# indicator.net
KiCad netlist of a schematic drawn in Altium Designer
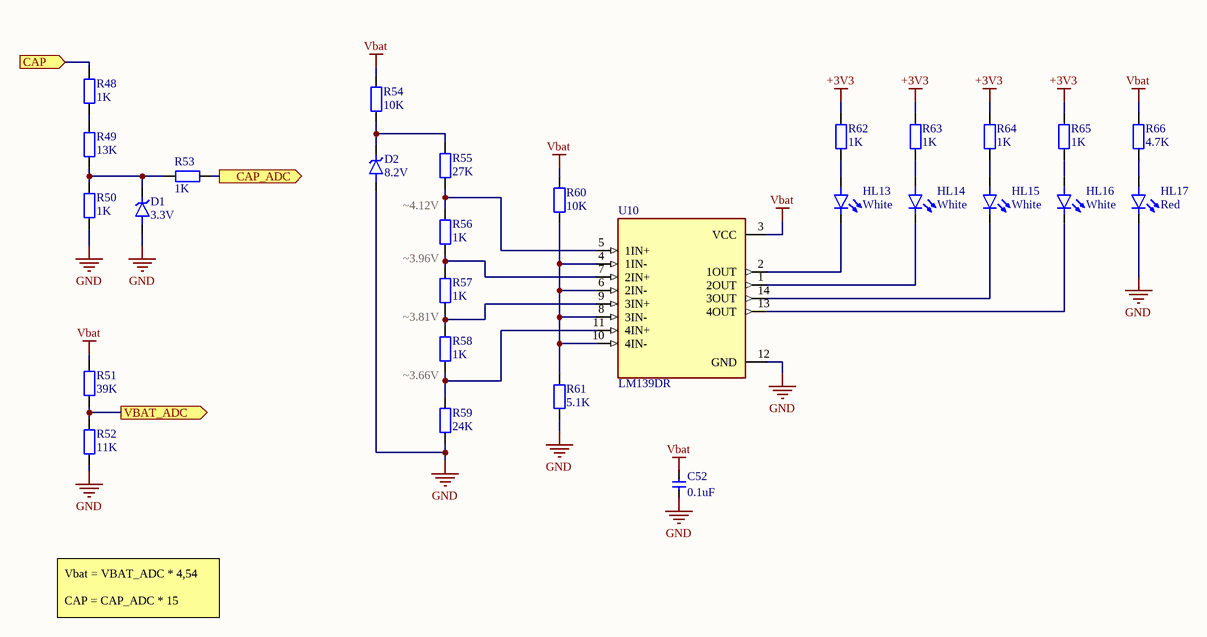
[diagram p0: indicator.SchDoc]

(export (version "E")
  (design (tool "Eeschema 10.0.6"))
  (components
    (comp (ref "C52")
      (value "0.1uF")
      (footprint "CAP0805")
      (description "Ceramic SMD Cap")
      (libsource (lib "Asterisk") (part "CAP Ceramic"))
    )
    (comp (ref "D1")
      (value "3.3V")
      (footprint "SOD-80")
      (description "Zener Diode\r\nBZV55C8V2")
      (libsource (lib "Asterisk") (part "Diode Zener"))
    )
    (comp (ref "D2")
      (value "8.2V")
      (footprint "SOD-80")
      (description "Zener Diode\r\nBZV55C8V2")
      (libsource (lib "Asterisk") (part "Diode Zener"))
    )
    (comp (ref "HL13")
      (value "White")
      (footprint "LED0603_GREEN")
      (description "LED smd")
      (libsource (lib "Asterisk") (part "LED"))
    )
    (comp (ref "HL14")
      (value "White")
      (footprint "LED0603_GREEN")
      (description "LED smd")
      (libsource (lib "Asterisk") (part "LED"))
    )
    (comp (ref "HL15")
      (value "White")
      (footprint "LED0603_GREEN")
      (description "LED smd")
      (libsource (lib "Asterisk") (part "LED"))
    )
    (comp (ref "HL16")
      (value "White")
      (footprint "LED0603_GREEN")
      (description "LED smd")
      (libsource (lib "Asterisk") (part "LED"))
    )
    (comp (ref "HL17")
      (value "Red")
      (footprint "LED0603_RED")
      (description "LED smd")
      (libsource (lib "Asterisk") (part "LED"))
    )
    (comp (ref "R48")
      (value "1K")
      (footprint "RES0805")
      (description "RES smd")
      (libsource (lib "Asterisk") (part "RES"))
    )
    (comp (ref "R49")
      (value "13K")
      (footprint "RES0805")
      (description "RES smd")
      (libsource (lib "Asterisk") (part "RES"))
    )
    (comp (ref "R50")
      (value "1K")
      (footprint "RES0805")
      (description "RES smd")
      (libsource (lib "Asterisk") (part "RES"))
    )
    (comp (ref "R51")
      (value "39K")
      (footprint "RES0805")
      (description "RES smd")
      (libsource (lib "Asterisk") (part "RES"))
    )
    (comp (ref "R52")
      (value "11K")
      (footprint "RES0805")
      (description "RES smd")
      (libsource (lib "Asterisk") (part "RES"))
    )
    (comp (ref "R53")
      (value "1K")
      (footprint "RES0805")
      (description "RES smd")
      (libsource (lib "Asterisk") (part "RES"))
    )
    (comp (ref "R54")
      (value "10K")
      (footprint "RES0805")
      (description "RES smd")
      (libsource (lib "Asterisk") (part "RES"))
    )
    (comp (ref "R55")
      (value "27K")
      (footprint "RES0805")
      (description "RES smd")
      (libsource (lib "Asterisk") (part "RES"))
    )
    (comp (ref "R56")
      (value "1K")
      (footprint "RES0805")
      (description "RES smd")
      (libsource (lib "Asterisk") (part "RES"))
    )
    (comp (ref "R57")
      (value "1K")
      (footprint "RES0805")
      (description "RES smd")
      (libsource (lib "Asterisk") (part "RES"))
    )
    (comp (ref "R58")
      (value "1K")
      (footprint "RES0805")
      (description "RES smd")
      (libsource (lib "Asterisk") (part "RES"))
    )
    (comp (ref "R59")
      (value "24K")
      (footprint "RES0805")
      (description "RES smd")
      (libsource (lib "Asterisk") (part "RES"))
    )
    (comp (ref "R60")
      (value "10K")
      (footprint "RES0805")
      (description "RES smd")
      (libsource (lib "Asterisk") (part "RES"))
    )
    (comp (ref "R61")
      (value "5.1K")
      (footprint "RES0805")
      (description "RES smd")
      (libsource (lib "Asterisk") (part "RES"))
    )
    (comp (ref "R62")
      (value "1K")
      (footprint "RES0805")
      (description "RES smd")
      (libsource (lib "Asterisk") (part "RES"))
    )
    (comp (ref "R63")
      (value "1K")
      (footprint "RES0805")
      (description "RES smd")
      (libsource (lib "Asterisk") (part "RES"))
    )
    (comp (ref "R64")
      (value "1K")
      (footprint "RES0805")
      (description "RES smd")
      (libsource (lib "Asterisk") (part "RES"))
    )
    (comp (ref "R65")
      (value "1K")
      (footprint "RES0805")
      (description "RES smd")
      (libsource (lib "Asterisk") (part "RES"))
    )
    (comp (ref "R66")
      (value "4.7K")
      (footprint "RES0805")
      (description "RES smd")
      (libsource (lib "Asterisk") (part "RES"))
    )
    (comp (ref "U10")
      (value "LM139DR")
      (footprint "SOIC-14")
      (description "Quad differential comparator")
      (libsource (lib "Asterisk") (part "LM139DR"))
    )
  )
  (nets
    (net (code "1") (name "+3V3") (class "Default")
      (node (ref "R62") (pin "2") (pinfunction "2_2") (pintype "passive"))
      (node (ref "R63") (pin "2") (pinfunction "2_2") (pintype "passive"))
      (node (ref "R64") (pin "2") (pinfunction "2_2") (pintype "passive"))
      (node (ref "R65") (pin "2") (pinfunction "2_2") (pintype "passive"))
    )
    (net (code "2") (name "/CAP") (class "Default")
      (node (ref "R48") (pin "2") (pinfunction "2_2") (pintype "passive"))
    )
    (net (code "3") (name "/CAP_ADC") (class "Default")
      (node (ref "R53") (pin "1") (pinfunction "1_1") (pintype "passive"))
    )
    (net (code "4") (name "/VBAT_ADC") (class "Default")
      (node (ref "R51") (pin "1") (pinfunction "1_1") (pintype "passive"))
      (node (ref "R52") (pin "2") (pinfunction "2_2") (pintype "passive"))
    )
    (net (code "5") (name "GND") (class "Default")
      (node (ref "C52") (pin "1") (pinfunction "1_1") (pintype "passive"))
      (node (ref "D1") (pin "A") (pinfunction "A_A") (pintype "passive"))
      (node (ref "D2") (pin "A") (pinfunction "A_A") (pintype "passive"))
      (node (ref "HL17") (pin "1") (pinfunction "K_1") (pintype "passive"))
      (node (ref "R50") (pin "1") (pinfunction "1_1") (pintype "passive"))
      (node (ref "R52") (pin "1") (pinfunction "1_1") (pintype "passive"))
      (node (ref "R59") (pin "1") (pinfunction "1_1") (pintype "passive"))
      (node (ref "R61") (pin "1") (pinfunction "1_1") (pintype "passive"))
      (node (ref "U10") (pin "12") (pinfunction "GND_12") (pintype "power_in"))
    )
    (net (code "6") (name "Net-(D1-PadK)") (class "Default")
      (node (ref "D1") (pin "K") (pinfunction "K_K") (pintype "passive"))
      (node (ref "R49") (pin "1") (pinfunction "1_1") (pintype "passive"))
      (node (ref "R50") (pin "2") (pinfunction "2_2") (pintype "passive"))
      (node (ref "R53") (pin "2") (pinfunction "2_2") (pintype "passive"))
    )
    (net (code "7") (name "Net-(D2-PadK)") (class "Default")
      (node (ref "D2") (pin "K") (pinfunction "K_K") (pintype "passive"))
      (node (ref "R54") (pin "1") (pinfunction "1_1") (pintype "passive"))
      (node (ref "R55") (pin "2") (pinfunction "2_2") (pintype "passive"))
    )
    (net (code "8") (name "Net-(HL13-A)") (class "Default")
      (node (ref "HL13") (pin "2") (pinfunction "A_2") (pintype "passive"))
      (node (ref "R62") (pin "1") (pinfunction "1_1") (pintype "passive"))
    )
    (net (code "9") (name "Net-(HL13-K)") (class "Default")
      (node (ref "HL13") (pin "1") (pinfunction "K_1") (pintype "passive"))
      (node (ref "U10") (pin "2") (pinfunction "1OUT_2") (pintype "output"))
    )
    (net (code "10") (name "Net-(HL14-A)") (class "Default")
      (node (ref "HL14") (pin "2") (pinfunction "A_2") (pintype "passive"))
      (node (ref "R63") (pin "1") (pinfunction "1_1") (pintype "passive"))
    )
    (net (code "11") (name "Net-(HL14-K)") (class "Default")
      (node (ref "HL14") (pin "1") (pinfunction "K_1") (pintype "passive"))
      (node (ref "U10") (pin "1") (pinfunction "2OUT_1") (pintype "output"))
    )
    (net (code "12") (name "Net-(HL15-A)") (class "Default")
      (node (ref "HL15") (pin "2") (pinfunction "A_2") (pintype "passive"))
      (node (ref "R64") (pin "1") (pinfunction "1_1") (pintype "passive"))
    )
    (net (code "13") (name "Net-(HL15-K)") (class "Default")
      (node (ref "HL15") (pin "1") (pinfunction "K_1") (pintype "passive"))
      (node (ref "U10") (pin "14") (pinfunction "3OUT_14") (pintype "output"))
    )
    (net (code "14") (name "Net-(HL16-A)") (class "Default")
      (node (ref "HL16") (pin "2") (pinfunction "A_2") (pintype "passive"))
      (node (ref "R65") (pin "1") (pinfunction "1_1") (pintype "passive"))
    )
    (net (code "15") (name "Net-(HL16-K)") (class "Default")
      (node (ref "HL16") (pin "1") (pinfunction "K_1") (pintype "passive"))
      (node (ref "U10") (pin "13") (pinfunction "4OUT_13") (pintype "output"))
    )
    (net (code "16") (name "Net-(HL17-A)") (class "Default")
      (node (ref "HL17") (pin "2") (pinfunction "A_2") (pintype "passive"))
      (node (ref "R66") (pin "1") (pinfunction "1_1") (pintype "passive"))
    )
    (net (code "17") (name "Net-(R48-Pad1)") (class "Default")
      (node (ref "R48") (pin "1") (pinfunction "1_1") (pintype "passive"))
      (node (ref "R49") (pin "2") (pinfunction "2_2") (pintype "passive"))
    )
    (net (code "18") (name "Net-(U10-1IN+)") (class "Default")
      (node (ref "R55") (pin "1") (pinfunction "1_1") (pintype "passive"))
      (node (ref "R56") (pin "2") (pinfunction "2_2") (pintype "passive"))
      (node (ref "U10") (pin "5") (pinfunction "1IN+_5") (pintype "input"))
    )
    (net (code "19") (name "Net-(U10-1IN-)") (class "Default")
      (node (ref "R60") (pin "1") (pinfunction "1_1") (pintype "passive"))
      (node (ref "R61") (pin "2") (pinfunction "2_2") (pintype "passive"))
      (node (ref "U10") (pin "10") (pinfunction "4IN-_10") (pintype "input"))
      (node (ref "U10") (pin "4") (pinfunction "1IN-_4") (pintype "input"))
      (node (ref "U10") (pin "6") (pinfunction "2IN-_6") (pintype "input"))
      (node (ref "U10") (pin "8") (pinfunction "3IN-_8") (pintype "input"))
    )
    (net (code "20") (name "Net-(U10-2IN+)") (class "Default")
      (node (ref "R56") (pin "1") (pinfunction "1_1") (pintype "passive"))
      (node (ref "R57") (pin "2") (pinfunction "2_2") (pintype "passive"))
      (node (ref "U10") (pin "7") (pinfunction "2IN+_7") (pintype "input"))
    )
    (net (code "21") (name "Net-(U10-3IN+)") (class "Default")
      (node (ref "R57") (pin "1") (pinfunction "1_1") (pintype "passive"))
      (node (ref "R58") (pin "2") (pinfunction "2_2") (pintype "passive"))
      (node (ref "U10") (pin "9") (pinfunction "3IN+_9") (pintype "input"))
    )
    (net (code "22") (name "Net-(U10-4IN+)") (class "Default")
      (node (ref "R58") (pin "1") (pinfunction "1_1") (pintype "passive"))
      (node (ref "R59") (pin "2") (pinfunction "2_2") (pintype "passive"))
      (node (ref "U10") (pin "11") (pinfunction "4IN+_11") (pintype "input"))
    )
    (net (code "23") (name "Vbat") (class "Default")
      (node (ref "C52") (pin "2") (pinfunction "2_2") (pintype "passive"))
      (node (ref "R51") (pin "2") (pinfunction "2_2") (pintype "passive"))
      (node (ref "R54") (pin "2") (pinfunction "2_2") (pintype "passive"))
      (node (ref "R60") (pin "2") (pinfunction "2_2") (pintype "passive"))
      (node (ref "R66") (pin "2") (pinfunction "2_2") (pintype "passive"))
      (node (ref "U10") (pin "3") (pinfunction "VCC_3") (pintype "power_in"))
    )
  )
)
